# EasyEDA.net
KiCad netlist of a schematic drawn in EasyEDA Pro
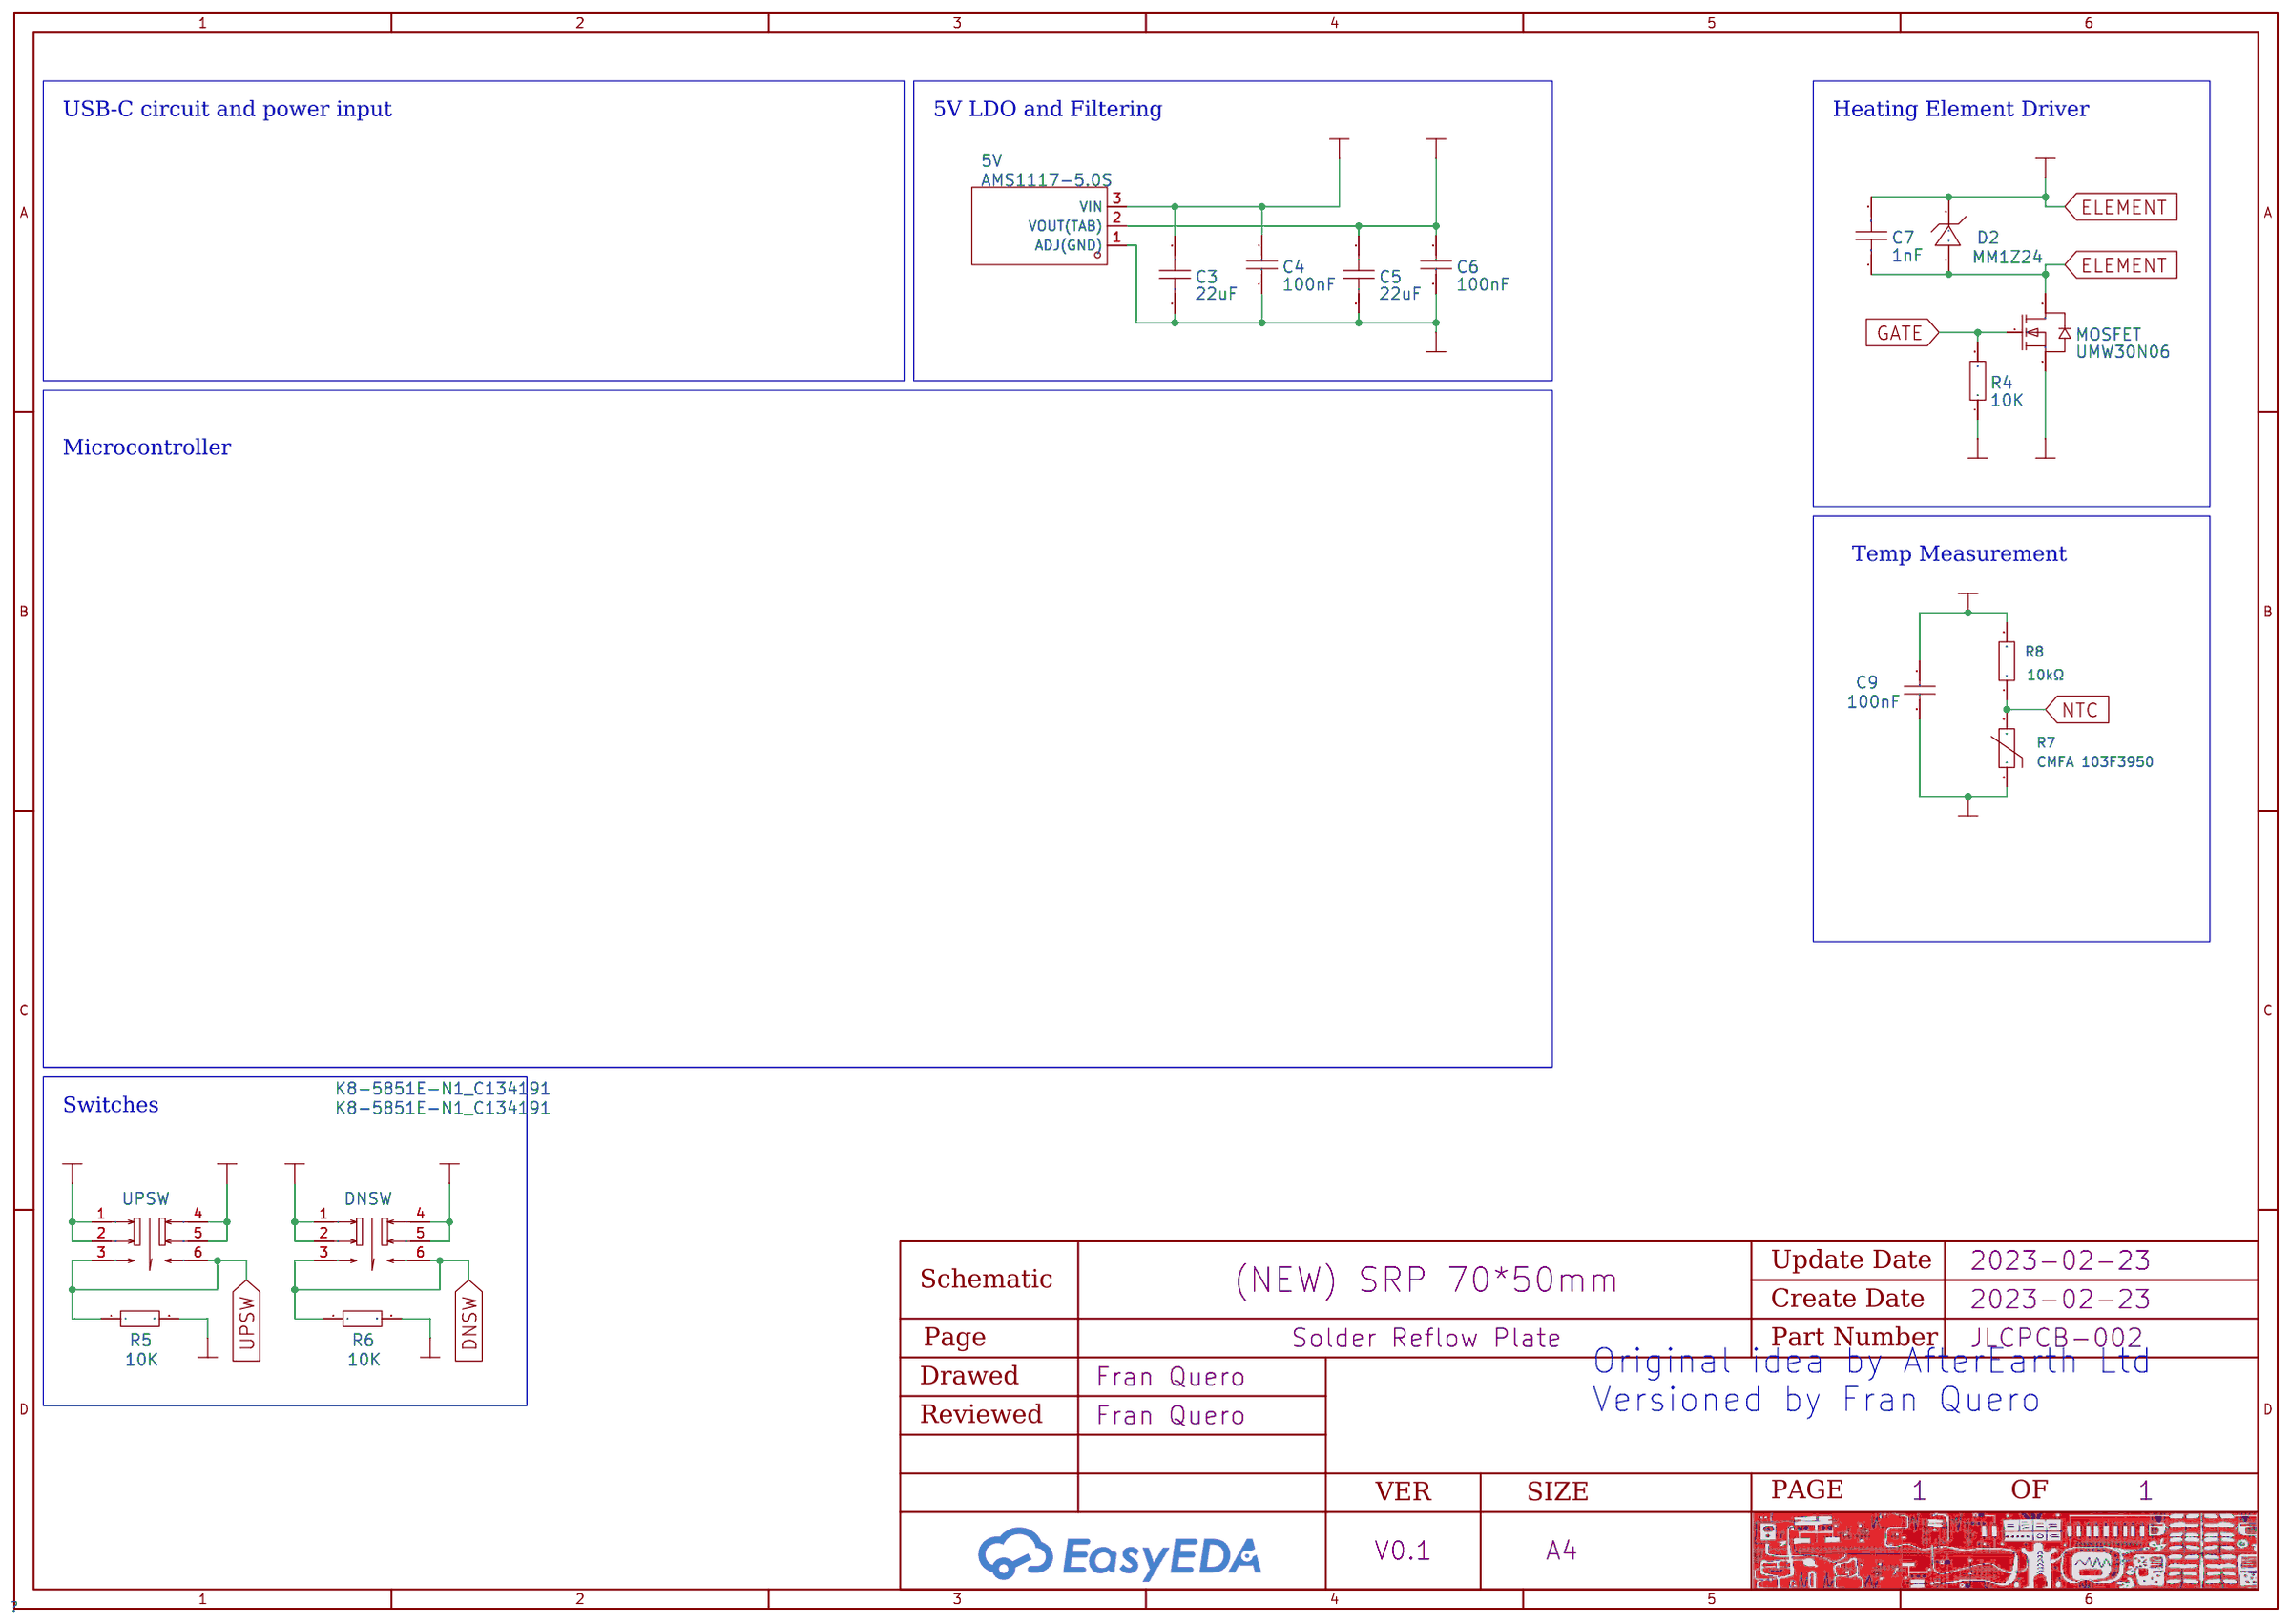
[diagram p0: schematic sheet]

(export (version "E")
  (design (tool "Eeschema 10.0.6"))
  (components
    (comp (ref "5V")
      (value "AMS1117-5.0S")
      (footprint "easyedapro:SOT-89_L4.5-W2.5-P1.50-LS4.2-BR")
      (fields (field (name "Manufacturer") "Youtai Semiconductor Co., Ltd."))
      (libsource (lib "easyedapro") (part "AMS1117-5.0S"))
    )
    (comp (ref "C3")
      (value "22uF")
      (footprint "easyedapro:C0805")
      (fields
        (field (name "Manufacturer Part") "CL21A226MAYNNNE")
        (field (name "Manufacturer") "Samsung Electro-Mechanics")
      )
      (libsource (lib "easyedapro") (part "22uF"))
    )
    (comp (ref "C4")
      (value "100nF")
      (footprint "easyedapro:C0603")
      (fields (field (name "Manufacturer Part") "0603B104K250") (field (name "Manufacturer") "WTC"))
      (libsource (lib "easyedapro") (part "100nF"))
    )
    (comp (ref "C5")
      (value "22uF")
      (footprint "easyedapro:C0805")
      (fields
        (field (name "Manufacturer Part") "CL21A226MAYNNNE")
        (field (name "Manufacturer") "Samsung Electro-Mechanics")
      )
      (libsource (lib "easyedapro") (part "22uF"))
    )
    (comp (ref "C6")
      (value "100nF")
      (footprint "easyedapro:C0603")
      (fields (field (name "Manufacturer Part") "0603B104K250") (field (name "Manufacturer") "WTC"))
      (libsource (lib "easyedapro") (part "100nF"))
    )
    (comp (ref "C7")
      (value "1nF")
      (footprint "easyedapro:C0805")
      (fields
        (field (name "Manufacturer Part") "FM21X102K501PXG")
        (field (name "Manufacturer") "PSA(Prosperity Dielectrics)")
      )
      (libsource (lib "easyedapro") (part "1nF"))
    )
    (comp (ref "C9")
      (value "100nF")
      (footprint "easyedapro:C0603")
      (fields (field (name "Manufacturer Part") "0603B104K250") (field (name "Manufacturer") "WTC"))
      (libsource (lib "easyedapro") (part "100nF"))
    )
    (comp (ref "D2")
      (value "MM1Z24")
      (footprint "easyedapro:SOD-123_L2.8-W1.8-LS3.7-FD")
      (fields (field (name "Manufacturer") "SEMTECH"))
      (libsource (lib "easyedapro") (part "MM1Z24"))
    )
    (comp (ref "DNSW")
      (value "K8-5851E-N1_C134191")
      (footprint "easyedapro:SW-TH_6P-L5.8-W5.8-P2.00-LS4.5-BL")
      (fields (field (name "Manufacturer Part") "K8-5851E-N1") (field (name "Manufacturer") "HRO"))
      (libsource (lib "easyedapro") (part "K8-5851E-N1_C134191"))
    )
    (comp (ref "MOSFET")
      (value "UMW30N06")
      (footprint "easyedapro:TO-252-2_L6.6-W6.1-P4.57-LS9.9-BR-CW")
      (fields (field (name "Manufacturer") "Youtai Semiconductor Co., Ltd."))
      (libsource (lib "easyedapro") (part "UMW30N06"))
    )
    (comp (ref "R4")
      (value "10K")
      (footprint "easyedapro:R0603")
      (fields (field (name "Manufacturer Part") "RTT03103JTP") (field (name "Manufacturer") "RALEC"))
      (libsource (lib "easyedapro") (part "10K"))
    )
    (comp (ref "R5")
      (value "10K")
      (footprint "easyedapro:R0603")
      (fields (field (name "Manufacturer Part") "RTT03103JTP") (field (name "Manufacturer") "RALEC"))
      (libsource (lib "easyedapro") (part "10K"))
    )
    (comp (ref "R6")
      (value "10K")
      (footprint "easyedapro:R0603")
      (fields (field (name "Manufacturer Part") "RTT03103JTP") (field (name "Manufacturer") "RALEC"))
      (libsource (lib "easyedapro") (part "10K"))
    )
    (comp (ref "R7")
      (value "CMFA 103F3950")
      (footprint "easyedapro:R0603")
      (fields (field (name "Manufacturer") "时恒"))
      (libsource (lib "easyedapro") (part "CMFA 103F3950"))
    )
    (comp (ref "R8")
      (value "10kΩ")
      (footprint "easyedapro:R0603")
      (fields (field (name "Manufacturer Part") "ARG03BTC1002") (field (name "Manufacturer") "Viking(光颉)"))
      (libsource (lib "easyedapro") (part "ARG03BTC1002"))
    )
    (comp (ref "UPSW")
      (value "K8-5851E-N1_C134191")
      (footprint "easyedapro:SW-TH_6P-L5.8-W5.8-P2.00-LS4.5-BL")
      (fields (field (name "Manufacturer Part") "K8-5851E-N1") (field (name "Manufacturer") "HRO"))
      (libsource (lib "easyedapro") (part "K8-5851E-N1_C134191"))
    )
  )
  (nets
    (net (code "1") (name "0V") (class "Default")
      (node (ref "5V") (pin "1") (pinfunction "ADJ(GND)_1") (pintype "input"))
      (node (ref "C3") (pin "1") (pinfunction "1_1") (pintype "input"))
      (node (ref "C4") (pin "2") (pinfunction "2_2") (pintype "input"))
      (node (ref "C5") (pin "1") (pinfunction "1_1") (pintype "input"))
      (node (ref "C6") (pin "2") (pinfunction "2_2") (pintype "input"))
      (node (ref "C9") (pin "2") (pinfunction "2_2") (pintype "input"))
      (node (ref "MOSFET") (pin "3") (pinfunction "S_3") (pintype "input"))
      (node (ref "R4") (pin "1") (pinfunction "1_1") (pintype "input"))
      (node (ref "R5") (pin "2") (pinfunction "2_2") (pintype "input"))
      (node (ref "R6") (pin "2") (pinfunction "2_2") (pintype "input"))
      (node (ref "R7") (pin "1") (pinfunction "1_1") (pintype "input"))
    )
    (net (code "2") (name "5V+") (class "Default")
      (node (ref "5V") (pin "2") (pinfunction "VOUT(TAB)_2") (pintype "input"))
      (node (ref "C5") (pin "2") (pinfunction "2_2") (pintype "input"))
      (node (ref "C6") (pin "1") (pinfunction "1_1") (pintype "input"))
      (node (ref "C9") (pin "1") (pinfunction "1_1") (pintype "input"))
      (node (ref "DNSW") (pin "1") (pinfunction "1_1") (pintype "input"))
      (node (ref "DNSW") (pin "2") (pinfunction "2_2") (pintype "input"))
      (node (ref "DNSW") (pin "4") (pinfunction "4_4") (pintype "input"))
      (node (ref "DNSW") (pin "5") (pinfunction "5_5") (pintype "input"))
      (node (ref "R8") (pin "2") (pinfunction "2_2") (pintype "input"))
      (node (ref "UPSW") (pin "1") (pinfunction "1_1") (pintype "input"))
      (node (ref "UPSW") (pin "2") (pinfunction "2_2") (pintype "input"))
      (node (ref "UPSW") (pin "4") (pinfunction "4_4") (pintype "input"))
      (node (ref "UPSW") (pin "5") (pinfunction "5_5") (pintype "input"))
    )
    (net (code "3") (name "DNSW") (class "Default")
      (node (ref "DNSW") (pin "3") (pinfunction "3_3") (pintype "input"))
      (node (ref "DNSW") (pin "6") (pinfunction "6_6") (pintype "input"))
      (node (ref "R6") (pin "1") (pinfunction "1_1") (pintype "input"))
    )
    (net (code "4") (name "ELEMENT") (class "Default")
      (node (ref "C7") (pin "1") (pinfunction "1_1") (pintype "input"))
      (node (ref "C7") (pin "2") (pinfunction "2_2") (pintype "input"))
      (node (ref "D2") (pin "1") (pinfunction "A_1") (pintype "input"))
      (node (ref "D2") (pin "2") (pinfunction "K_2") (pintype "input"))
      (node (ref "MOSFET") (pin "2") (pinfunction "D_2") (pintype "input"))
    )
    (net (code "5") (name "GATE") (class "Default")
      (node (ref "MOSFET") (pin "1") (pinfunction "G_1") (pintype "input"))
      (node (ref "R4") (pin "2") (pinfunction "2_2") (pintype "input"))
    )
    (net (code "6") (name "NTC") (class "Default")
      (node (ref "R7") (pin "2") (pinfunction "2_2") (pintype "input"))
      (node (ref "R8") (pin "1") (pinfunction "1_1") (pintype "input"))
    )
    (net (code "7") (name "UPSW") (class "Default")
      (node (ref "R5") (pin "1") (pinfunction "1_1") (pintype "input"))
      (node (ref "UPSW") (pin "3") (pinfunction "3_3") (pintype "input"))
      (node (ref "UPSW") (pin "6") (pinfunction "6_6") (pintype "input"))
    )
    (net (code "8") (name "VIN-D") (class "Default")
      (node (ref "5V") (pin "3") (pinfunction "VIN_3") (pintype "input"))
      (node (ref "C3") (pin "2") (pinfunction "2_2") (pintype "input"))
      (node (ref "C4") (pin "1") (pinfunction "1_1") (pintype "input"))
    )
  )
)
